# Switch.net
KiCad netlist of a schematic drawn in Altium Designer
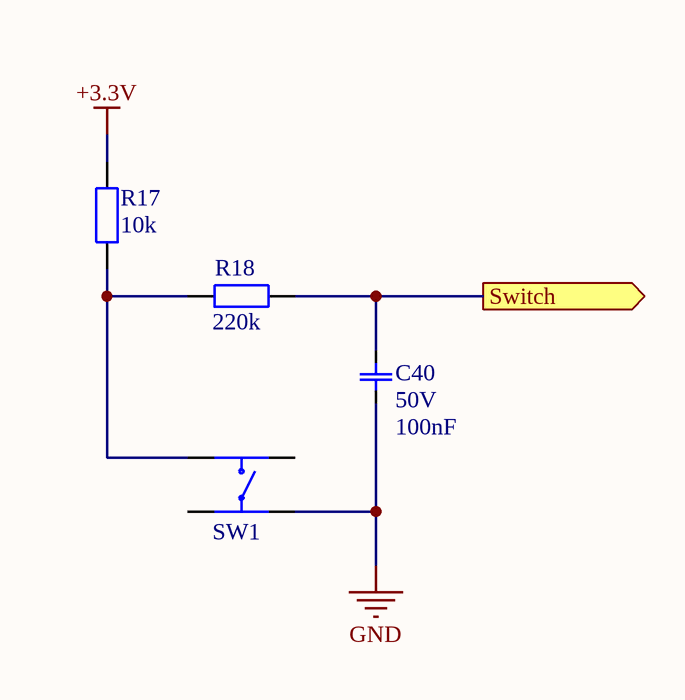
[diagram p0: Switch.SchDoc]

(export (version "E")
  (design (tool "Eeschema 10.0.6"))
  (components
    (comp (ref "C40")
      (value "100nF")
      (footprint "MLCC_0603")
      (description "MLCC 100nF 50V 0603")
      (fields (field (name "VOLTAGE") "50V"))
      (libsource (lib "Nixie") (part "MLCC 100nF 50V 0603"))
    )
    (comp (ref "R17")
      (value "10k")
      (footprint "RES0805")
      (description "Chip resistor 10k 0805")
      (libsource (lib "Nixie") (part "10k 0805"))
    )
    (comp (ref "R18")
      (value "220k")
      (footprint "RES0805")
      (description "Chip resistor 220k 0805")
      (libsource (lib "Nixie") (part "220k 0805"))
    )
    (comp (ref "SW1")
      (value "KSEK43GLFS")
      (footprint "KSEK43GLFS")
      (description "Low Profile Tact Switch, 4.3 mm height")
      (libsource (lib "Nixie") (part "KSEK43GLFS"))
    )
  )
  (nets
    (net (code "1") (name "+3.3V") (class "Default")
      (node (ref "R17") (pin "2") (pinfunction "2_2") (pintype "passive"))
    )
    (net (code "2") (name "/Switch") (class "Default")
      (node (ref "C40") (pin "1") (pinfunction "1_1") (pintype "passive"))
      (node (ref "R18") (pin "2") (pinfunction "2_2") (pintype "passive"))
    )
    (net (code "3") (name "GND") (class "Default")
      (node (ref "C40") (pin "2") (pinfunction "2_2") (pintype "passive"))
      (node (ref "SW1") (pin "3") (pinfunction "3_3") (pintype "passive"))
    )
    (net (code "4") (name "Net-(R17-Pad1)") (class "Default")
      (node (ref "R17") (pin "1") (pinfunction "1_1") (pintype "passive"))
      (node (ref "R18") (pin "1") (pinfunction "1_1") (pintype "passive"))
      (node (ref "SW1") (pin "1") (pinfunction "1_1") (pintype "passive"))
    )
    (net (code "5") (name "unconnected-(SW1-Pad2)") (class "Default")
      (node (ref "SW1") (pin "2") (pinfunction "2_2") (pintype "passive"))
    )
    (net (code "6") (name "unconnected-(SW1-Pad4)") (class "Default")
      (node (ref "SW1") (pin "4") (pinfunction "4_4") (pintype "passive"))
    )
  )
)
